# Sheet1.net
KiCad netlist of a schematic drawn in Altium Designer
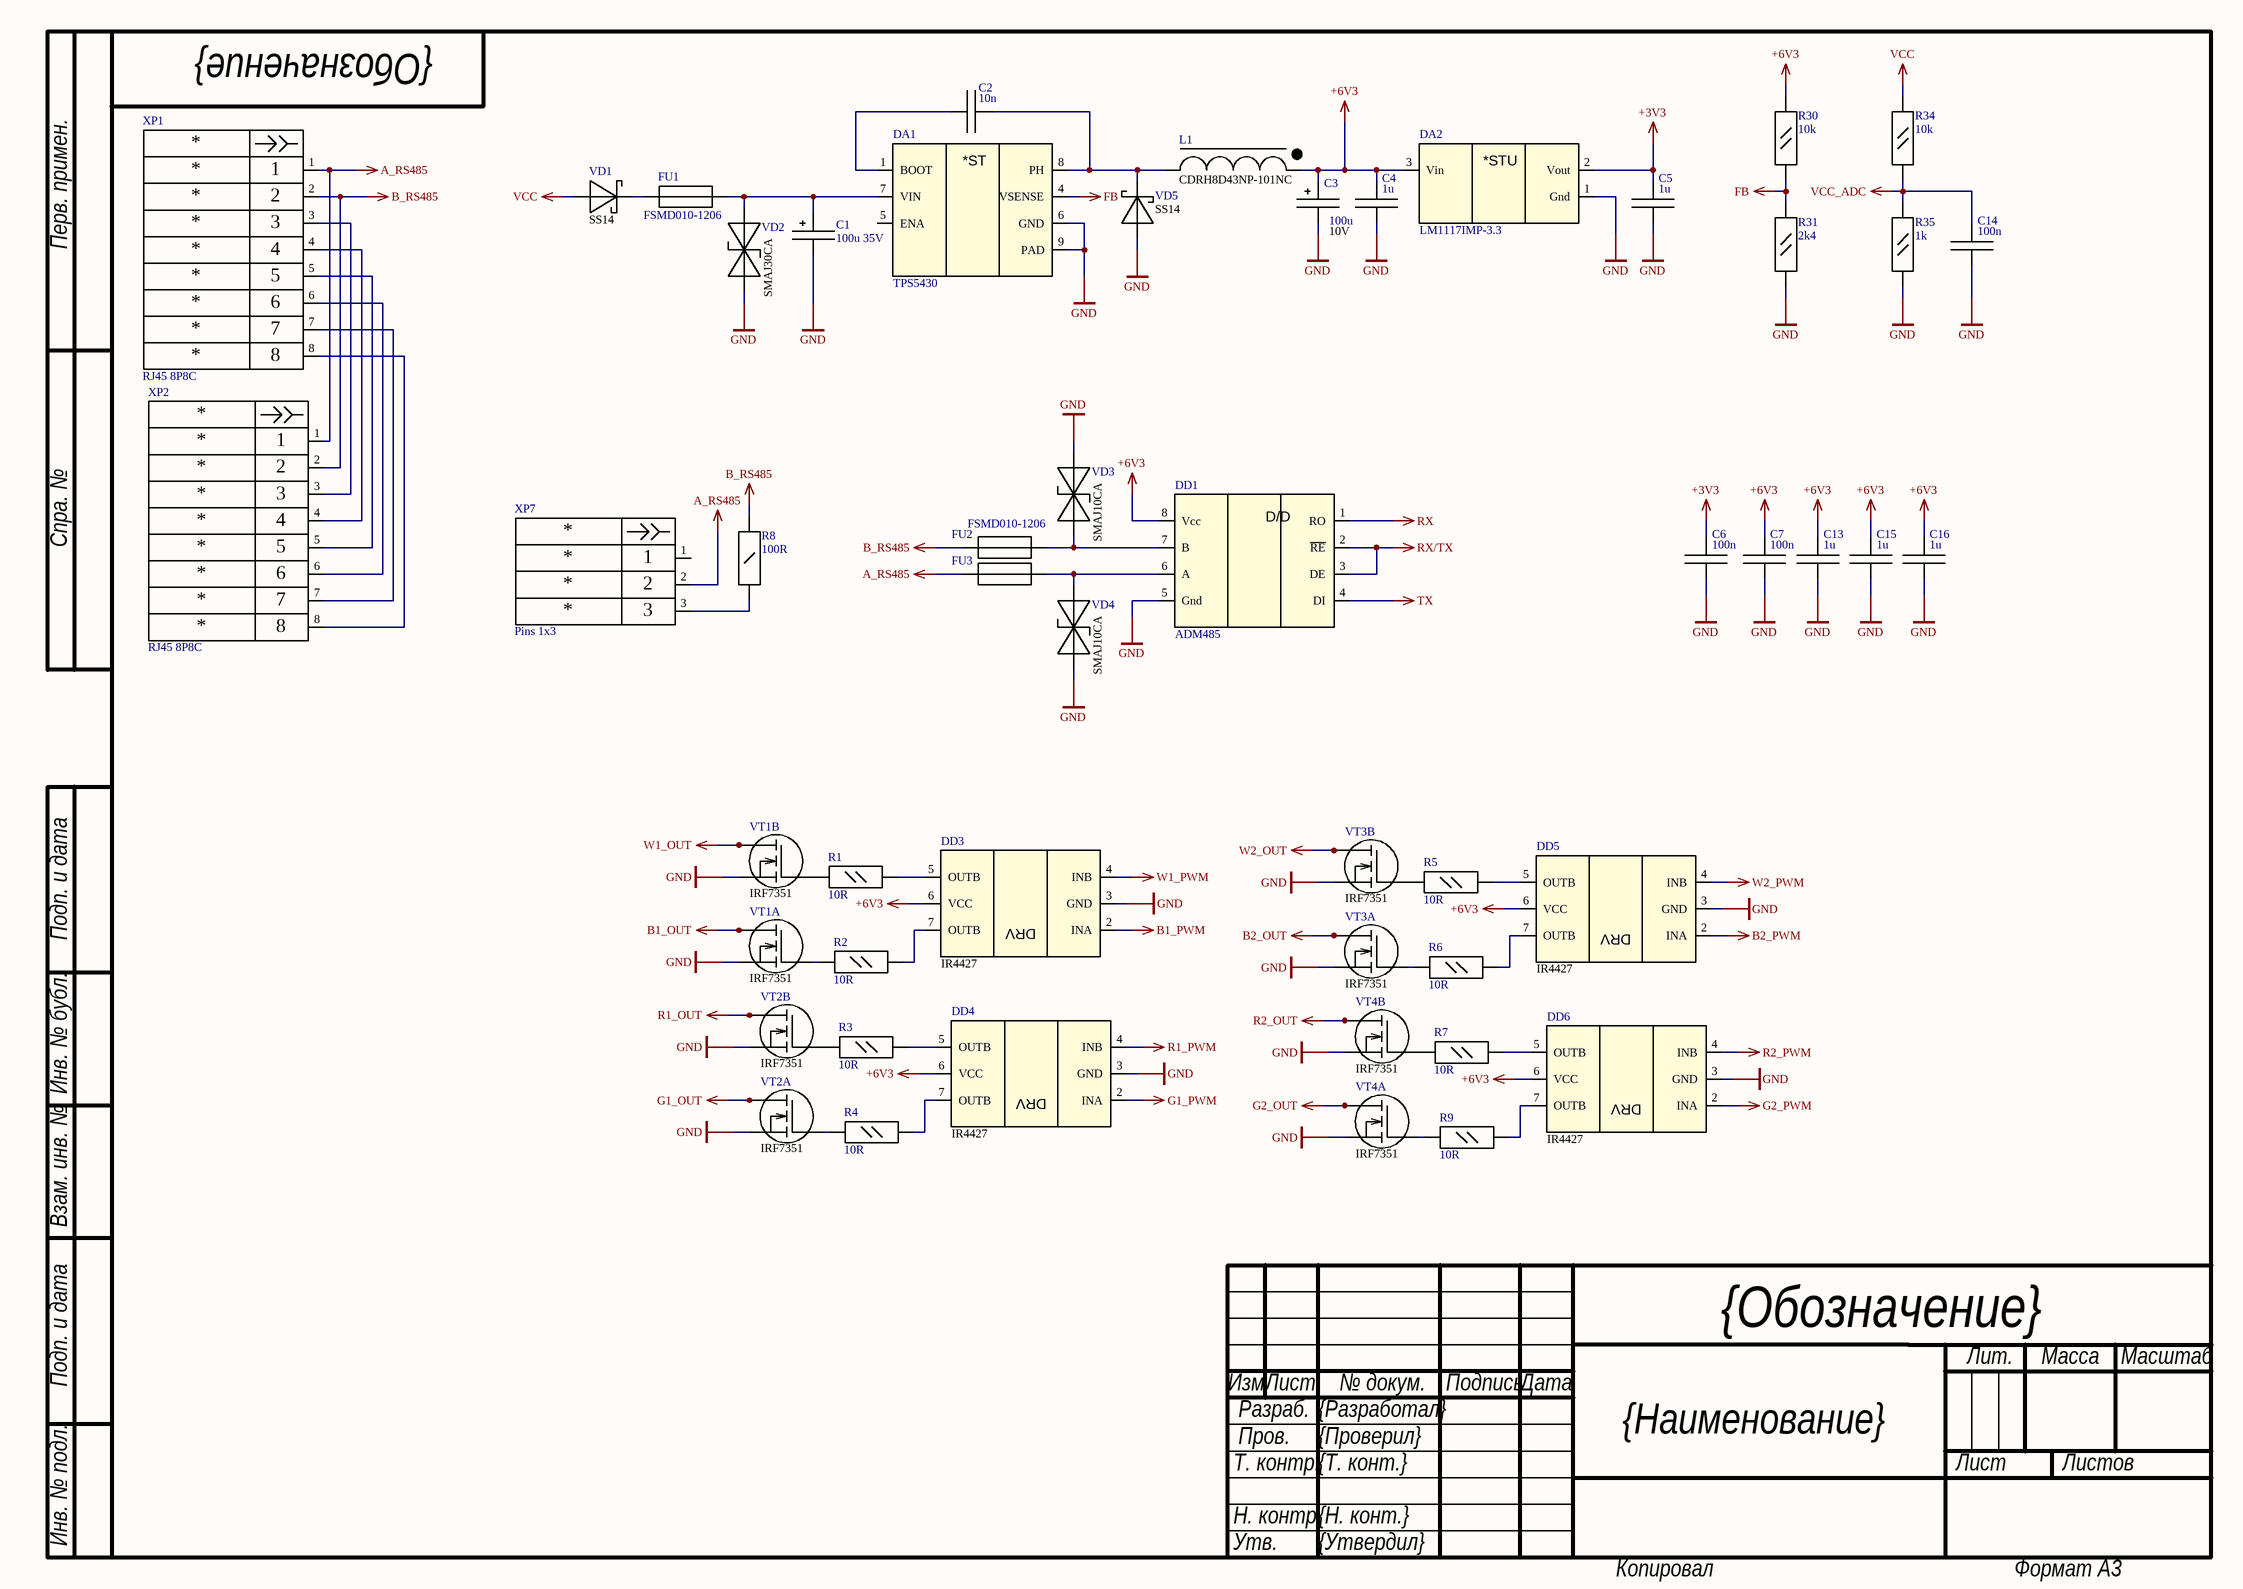
[diagram p0: Sheet1.SchDoc]

(export (version "E")
  (design (tool "Eeschema 10.0.6"))
  (components
    (comp (ref "C1")
      (value "100u 35V")
      (footprint "Cap electro d6.3x2.54mm")
      (libsource (lib "Россыпь") (part "ECap"))
    )
    (comp (ref "C2") (value "10n") (footprint "Cap Ceramic 0805") (libsource (lib "Россыпь") (part "CerCap")))
    (comp (ref "C3")
      (value "100u")
      (footprint "TECap D")
      (fields (field (name "COMMENTS") "10V"))
      (libsource (lib "Россыпь") (part "TECap"))
    )
    (comp (ref "C4") (value "1u") (footprint "Cap Ceramic 0805") (libsource (lib "Россыпь") (part "CerCap")))
    (comp (ref "C5") (value "1u") (footprint "Cap Ceramic 0805") (libsource (lib "Россыпь") (part "CerCap")))
    (comp (ref "C6")
      (value "100n")
      (footprint "Cap Ceramic 0805")
      (libsource (lib "Россыпь") (part "CerCap"))
    )
    (comp (ref "C7")
      (value "100n")
      (footprint "Cap Ceramic 0805")
      (libsource (lib "Россыпь") (part "CerCap"))
    )
    (comp (ref "C13") (value "1u") (footprint "Cap Ceramic 0805") (libsource (lib "Россыпь") (part "CerCap")))
    (comp (ref "C14")
      (value "100n")
      (footprint "Cap Ceramic 0805")
      (libsource (lib "Россыпь") (part "CerCap"))
    )
    (comp (ref "C15") (value "1u") (footprint "Cap Ceramic 0805") (libsource (lib "Россыпь") (part "CerCap")))
    (comp (ref "C16") (value "1u") (footprint "Cap Ceramic 0805") (libsource (lib "Россыпь") (part "CerCap")))
    (comp (ref "DA1")
      (value "TPS5430")
      (footprint "SO8 S1.27W6.00 GP")
      (libsource (lib "Россыпь") (part "TPS5430"))
    )
    (comp (ref "DA2")
      (value "LM1117IMP-3.3")
      (footprint "SOT-232")
      (libsource (lib "Россыпь") (part "LM1117IMP-x.x"))
    )
    (comp (ref "DD1")
      (value "ADM485")
      (footprint "SO8 S1.27W6.00")
      (libsource (lib "Россыпь") (part "ADM485"))
    )
    (comp (ref "DD3")
      (value "IR4427")
      (footprint "SO8 S1.27W6.00")
      (libsource (lib "Россыпь") (part "IR4427"))
    )
    (comp (ref "DD4")
      (value "IR4427")
      (footprint "SO8 S1.27W6.00")
      (libsource (lib "Россыпь") (part "IR4427"))
    )
    (comp (ref "DD5")
      (value "IR4427")
      (footprint "SO8 S1.27W6.00")
      (libsource (lib "Россыпь") (part "IR4427"))
    )
    (comp (ref "DD6")
      (value "IR4427")
      (footprint "SO8 S1.27W6.00")
      (libsource (lib "Россыпь") (part "IR4427"))
    )
    (comp (ref "FU1")
      (value "FSMD010-1206")
      (footprint "Fuse 1206")
      (libsource (lib "Россыпь") (part "FSMDxxx-1206"))
    )
    (comp (ref "FU2")
      (value "FSMD010-1206")
      (footprint "Fuse 1206")
      (libsource (lib "Россыпь") (part "FSMDxxx-1206"))
    )
    (comp (ref "FU3")
      (value "FSMD010-1206")
      (footprint "Fuse 1206")
      (libsource (lib "Россыпь") (part "FSMDxxx-1206"))
    )
    (comp (ref "L1")
      (value "CDRH8D43NP-101NC")
      (footprint "CDRH8D43NP-xxxNC")
      (libsource (lib "Россыпь") (part "CDRH8D43NP-xxxNC"))
    )
    (comp (ref "R1")
      (value "10R")
      (footprint "Resistor 0805")
      (libsource (lib "Россыпь") (part "Resistor 0,125W"))
    )
    (comp (ref "R2")
      (value "10R")
      (footprint "Resistor 0805")
      (libsource (lib "Россыпь") (part "Resistor 0,125W"))
    )
    (comp (ref "R3")
      (value "10R")
      (footprint "Resistor 0805")
      (libsource (lib "Россыпь") (part "Resistor 0,125W"))
    )
    (comp (ref "R4")
      (value "10R")
      (footprint "Resistor 0805")
      (libsource (lib "Россыпь") (part "Resistor 0,125W"))
    )
    (comp (ref "R5")
      (value "10R")
      (footprint "Resistor 0805")
      (libsource (lib "Россыпь") (part "Resistor 0,125W"))
    )
    (comp (ref "R6")
      (value "10R")
      (footprint "Resistor 0805")
      (libsource (lib "Россыпь") (part "Resistor 0,125W"))
    )
    (comp (ref "R7")
      (value "10R")
      (footprint "Resistor 0805")
      (libsource (lib "Россыпь") (part "Resistor 0,125W"))
    )
    (comp (ref "R8")
      (value "100R")
      (footprint "Resistor 1206")
      (libsource (lib "Россыпь") (part "Resistor 0,25W"))
    )
    (comp (ref "R9")
      (value "10R")
      (footprint "Resistor 0805")
      (libsource (lib "Россыпь") (part "Resistor 0,125W"))
    )
    (comp (ref "R30")
      (value "10k")
      (footprint "Resistor 0805")
      (libsource (lib "Россыпь") (part "Resistor 0,125W"))
    )
    (comp (ref "R31")
      (value "2k4")
      (footprint "Resistor 0805")
      (libsource (lib "Россыпь") (part "Resistor 0,125W"))
    )
    (comp (ref "R34")
      (value "10k")
      (footprint "Resistor 0805")
      (libsource (lib "Россыпь") (part "Resistor 0,125W"))
    )
    (comp (ref "R35")
      (value "1k")
      (footprint "Resistor 0805")
      (libsource (lib "Россыпь") (part "Resistor 0,125W"))
    )
    (comp (ref "VD1") (value "SS14") (footprint "DO-214AC SMA") (libsource (lib "Россыпь") (part "SS14")))
    (comp (ref "VD2")
      (value "SMAJ30CA")
      (footprint "DO-214AC SMA")
      (libsource (lib "Россыпь") (part "SMAJxxCA"))
    )
    (comp (ref "VD3")
      (value "SMAJ10CA")
      (footprint "DO-214AC SMA")
      (libsource (lib "Россыпь") (part "SMAJxxCA"))
    )
    (comp (ref "VD4")
      (value "SMAJ10CA")
      (footprint "DO-214AC SMA")
      (libsource (lib "Россыпь") (part "SMAJxxCA"))
    )
    (comp (ref "VD5") (value "SS14") (footprint "DO-214AC SMA") (libsource (lib "Россыпь") (part "SS14")))
    (comp (ref "VT1")
      (value "IRF7351")
      (footprint "SO8 S1.27W6.00")
      (libsource (lib "Россыпь") (part "IRF7351"))
    )
    (comp (ref "VT2")
      (value "IRF7351")
      (footprint "SO8 S1.27W6.00")
      (libsource (lib "Россыпь") (part "IRF7351"))
    )
    (comp (ref "VT3")
      (value "IRF7351")
      (footprint "SO8 S1.27W6.00")
      (libsource (lib "Россыпь") (part "IRF7351"))
    )
    (comp (ref "VT4")
      (value "IRF7351")
      (footprint "SO8 S1.27W6.00")
      (libsource (lib "Россыпь") (part "IRF7351"))
    )
    (comp (ref "XP1")
      (value "RJ45 8P8C")
      (footprint "RJ45 8P8C")
      (fields
        (field (name "NAME1") "*")
        (field (name "NAME2") "*")
        (field (name "NAME3") "*")
        (field (name "NAME") "*")
        (field (name "NAME4") "*")
        (field (name "NAME5") "*")
        (field (name "NAME6") "*")
        (field (name "NAME7") "*")
        (field (name "NAME8") "*")
      )
      (libsource (lib "Россыпь") (part "RJ45 8P8C"))
    )
    (comp (ref "XP2")
      (value "RJ45 8P8C")
      (footprint "RJ45 8P8C")
      (fields
        (field (name "NAME1") "*")
        (field (name "NAME2") "*")
        (field (name "NAME3") "*")
        (field (name "NAME") "*")
        (field (name "NAME4") "*")
        (field (name "NAME5") "*")
        (field (name "NAME6") "*")
        (field (name "NAME7") "*")
        (field (name "NAME8") "*")
      )
      (libsource (lib "Россыпь") (part "RJ45 8P8C"))
    )
    (comp (ref "XP7")
      (value "Pins 1x3")
      (footprint "Pins 1x3")
      (fields
        (field (name "NAME1") "*")
        (field (name "NAME") "*")
        (field (name "NAME2") "*")
        (field (name "NAME3") "*")
      )
      (libsource (lib "Россыпь") (part "Pins 1x3"))
    )
  )
  (nets
    (net (code "1") (name "+3V3") (class "Default")
      (node (ref "C5") (pin "2") (pinfunction "2_2") (pintype "passive"))
      (node (ref "C6") (pin "2") (pinfunction "2_2") (pintype "passive"))
      (node (ref "DA2") (pin "2") (pinfunction "Vout_2") (pintype "passive"))
    )
    (net (code "2") (name "+6V3") (class "Default")
      (node (ref "C13") (pin "2") (pinfunction "2_2") (pintype "passive"))
      (node (ref "C15") (pin "2") (pinfunction "2_2") (pintype "passive"))
      (node (ref "C16") (pin "2") (pinfunction "2_2") (pintype "passive"))
      (node (ref "C3") (pin "2") (pinfunction "2_2") (pintype "passive"))
      (node (ref "C4") (pin "2") (pinfunction "2_2") (pintype "passive"))
      (node (ref "C7") (pin "2") (pinfunction "2_2") (pintype "passive"))
      (node (ref "DA2") (pin "3") (pinfunction "Vin_3") (pintype "passive"))
      (node (ref "DD1") (pin "8") (pinfunction "Vcc_8") (pintype "passive"))
      (node (ref "DD3") (pin "6") (pinfunction "VCC_6") (pintype "passive"))
      (node (ref "DD4") (pin "6") (pinfunction "VCC_6") (pintype "passive"))
      (node (ref "DD5") (pin "6") (pinfunction "VCC_6") (pintype "passive"))
      (node (ref "DD6") (pin "6") (pinfunction "VCC_6") (pintype "passive"))
      (node (ref "L1") (pin "1") (pinfunction "1_1") (pintype "passive"))
      (node (ref "R30") (pin "1") (pinfunction "1_1") (pintype "passive"))
    )
    (net (code "3") (name "A_RS485") (class "Default")
      (node (ref "FU3") (pin "1") (pinfunction "1_1") (pintype "passive"))
      (node (ref "XP1") (pin "1") (pinfunction "1_1") (pintype "passive"))
      (node (ref "XP2") (pin "1") (pinfunction "1_1") (pintype "passive"))
      (node (ref "XP7") (pin "2") (pinfunction "2_2") (pintype "passive"))
    )
    (net (code "4") (name "B1_OUT") (class "Default")
      (node (ref "VT1") (pin "7") (pinfunction "D1_7") (pintype "passive"))
      (node (ref "VT1") (pin "8") (pinfunction "D1_8") (pintype "passive"))
    )
    (net (code "5") (name "B1_PWM") (class "Default")
      (node (ref "DD3") (pin "2") (pinfunction "INA_2") (pintype "passive"))
    )
    (net (code "6") (name "B2_OUT") (class "Default")
      (node (ref "VT3") (pin "7") (pinfunction "D1_7") (pintype "passive"))
      (node (ref "VT3") (pin "8") (pinfunction "D1_8") (pintype "passive"))
    )
    (net (code "7") (name "B2_PWM") (class "Default")
      (node (ref "DD5") (pin "2") (pinfunction "INA_2") (pintype "passive"))
    )
    (net (code "8") (name "B_RS485") (class "Default")
      (node (ref "FU2") (pin "1") (pinfunction "1_1") (pintype "passive"))
      (node (ref "R8") (pin "2") (pinfunction "2_2") (pintype "passive"))
      (node (ref "XP1") (pin "2") (pinfunction "2_2") (pintype "passive"))
      (node (ref "XP2") (pin "2") (pinfunction "2_2") (pintype "passive"))
    )
    (net (code "9") (name "FB") (class "Default")
      (node (ref "DA1") (pin "4") (pinfunction "VSENSE_4") (pintype "passive"))
      (node (ref "R30") (pin "2") (pinfunction "2_2") (pintype "passive"))
      (node (ref "R31") (pin "1") (pinfunction "1_1") (pintype "passive"))
    )
    (net (code "10") (name "G1_OUT") (class "Default")
      (node (ref "VT2") (pin "7") (pinfunction "D1_7") (pintype "passive"))
      (node (ref "VT2") (pin "8") (pinfunction "D1_8") (pintype "passive"))
    )
    (net (code "11") (name "G1_PWM") (class "Default")
      (node (ref "DD4") (pin "2") (pinfunction "INA_2") (pintype "passive"))
    )
    (net (code "12") (name "G2_OUT") (class "Default")
      (node (ref "VT4") (pin "7") (pinfunction "D1_7") (pintype "passive"))
      (node (ref "VT4") (pin "8") (pinfunction "D1_8") (pintype "passive"))
    )
    (net (code "13") (name "G2_PWM") (class "Default")
      (node (ref "DD6") (pin "2") (pinfunction "INA_2") (pintype "passive"))
    )
    (net (code "14") (name "GND") (class "Default")
      (node (ref "C1") (pin "1") (pinfunction "1_1") (pintype "passive"))
      (node (ref "C13") (pin "1") (pinfunction "1_1") (pintype "passive"))
      (node (ref "C14") (pin "1") (pinfunction "1_1") (pintype "passive"))
      (node (ref "C15") (pin "1") (pinfunction "1_1") (pintype "passive"))
      (node (ref "C16") (pin "1") (pinfunction "1_1") (pintype "passive"))
      (node (ref "C3") (pin "1") (pinfunction "1_1") (pintype "passive"))
      (node (ref "C4") (pin "1") (pinfunction "1_1") (pintype "passive"))
      (node (ref "C5") (pin "1") (pinfunction "1_1") (pintype "passive"))
      (node (ref "C6") (pin "1") (pinfunction "1_1") (pintype "passive"))
      (node (ref "C7") (pin "1") (pinfunction "1_1") (pintype "passive"))
      (node (ref "DA1") (pin "6") (pinfunction "GND_6") (pintype "passive"))
      (node (ref "DA1") (pin "9") (pinfunction "PAD_9") (pintype "passive"))
      (node (ref "DA2") (pin "1") (pinfunction "Gnd_1") (pintype "passive"))
      (node (ref "DD1") (pin "5") (pinfunction "Gnd_5") (pintype "passive"))
      (node (ref "DD3") (pin "3") (pinfunction "GND_3") (pintype "passive"))
      (node (ref "DD4") (pin "3") (pinfunction "GND_3") (pintype "passive"))
      (node (ref "DD5") (pin "3") (pinfunction "GND_3") (pintype "passive"))
      (node (ref "DD6") (pin "3") (pinfunction "GND_3") (pintype "passive"))
      (node (ref "R31") (pin "2") (pinfunction "2_2") (pintype "passive"))
      (node (ref "R35") (pin "2") (pinfunction "2_2") (pintype "passive"))
      (node (ref "VD2") (pin "1") (pinfunction "1_1") (pintype "passive"))
      (node (ref "VD3") (pin "1") (pinfunction "1_1") (pintype "passive"))
      (node (ref "VD4") (pin "1") (pinfunction "1_1") (pintype "passive"))
      (node (ref "VD5") (pin "1") (pinfunction "A_1") (pintype "passive"))
      (node (ref "VT1") (pin "1") (pinfunction "S1_1") (pintype "passive"))
      (node (ref "VT1") (pin "3") (pinfunction "S2_3") (pintype "passive"))
      (node (ref "VT2") (pin "1") (pinfunction "S1_1") (pintype "passive"))
      (node (ref "VT2") (pin "3") (pinfunction "S2_3") (pintype "passive"))
      (node (ref "VT3") (pin "1") (pinfunction "S1_1") (pintype "passive"))
      (node (ref "VT3") (pin "3") (pinfunction "S2_3") (pintype "passive"))
      (node (ref "VT4") (pin "1") (pinfunction "S1_1") (pintype "passive"))
      (node (ref "VT4") (pin "3") (pinfunction "S2_3") (pintype "passive"))
    )
    (net (code "15") (name "Net-(DA1-BOOT)") (class "Default")
      (node (ref "C2") (pin "1") (pinfunction "1_1") (pintype "passive"))
      (node (ref "DA1") (pin "1") (pinfunction "BOOT_1") (pintype "passive"))
    )
    (net (code "16") (name "Net-(DA1-PH)") (class "Default")
      (node (ref "C2") (pin "2") (pinfunction "2_2") (pintype "passive"))
      (node (ref "DA1") (pin "8") (pinfunction "PH_8") (pintype "passive"))
      (node (ref "L1") (pin "2") (pinfunction "2_2") (pintype "passive"))
      (node (ref "VD5") (pin "2") (pinfunction "K_2") (pintype "passive"))
    )
    (net (code "17") (name "Net-(DA1-VIN)") (class "Default")
      (node (ref "C1") (pin "2") (pinfunction "2_2") (pintype "passive"))
      (node (ref "DA1") (pin "7") (pinfunction "VIN_7") (pintype "passive"))
      (node (ref "FU1") (pin "2") (pinfunction "2_2") (pintype "passive"))
      (node (ref "VD2") (pin "2") (pinfunction "2_2") (pintype "passive"))
    )
    (net (code "18") (name "Net-(DD1-A)") (class "Default")
      (node (ref "DD1") (pin "6") (pinfunction "A_6") (pintype "passive"))
      (node (ref "FU3") (pin "2") (pinfunction "2_2") (pintype "passive"))
      (node (ref "VD4") (pin "2") (pinfunction "2_2") (pintype "passive"))
    )
    (net (code "19") (name "Net-(DD1-B)") (class "Default")
      (node (ref "DD1") (pin "7") (pinfunction "B_7") (pintype "passive"))
      (node (ref "FU2") (pin "2") (pinfunction "2_2") (pintype "passive"))
      (node (ref "VD3") (pin "2") (pinfunction "2_2") (pintype "passive"))
    )
    (net (code "20") (name "Net-(DD3-OUTB-Pad5)") (class "Default")
      (node (ref "DD3") (pin "5") (pinfunction "OUTB_5") (pintype "passive"))
      (node (ref "R1") (pin "2") (pinfunction "2_2") (pintype "passive"))
    )
    (net (code "21") (name "Net-(DD3-OUTB-Pad7)") (class "Default")
      (node (ref "DD3") (pin "7") (pinfunction "OUTB_7") (pintype "passive"))
      (node (ref "R2") (pin "2") (pinfunction "2_2") (pintype "passive"))
    )
    (net (code "22") (name "Net-(DD4-OUTB-Pad5)") (class "Default")
      (node (ref "DD4") (pin "5") (pinfunction "OUTB_5") (pintype "passive"))
      (node (ref "R3") (pin "2") (pinfunction "2_2") (pintype "passive"))
    )
    (net (code "23") (name "Net-(DD4-OUTB-Pad7)") (class "Default")
      (node (ref "DD4") (pin "7") (pinfunction "OUTB_7") (pintype "passive"))
      (node (ref "R4") (pin "2") (pinfunction "2_2") (pintype "passive"))
    )
    (net (code "24") (name "Net-(DD5-OUTB-Pad5)") (class "Default")
      (node (ref "DD5") (pin "5") (pinfunction "OUTB_5") (pintype "passive"))
      (node (ref "R5") (pin "2") (pinfunction "2_2") (pintype "passive"))
    )
    (net (code "25") (name "Net-(DD5-OUTB-Pad7)") (class "Default")
      (node (ref "DD5") (pin "7") (pinfunction "OUTB_7") (pintype "passive"))
      (node (ref "R6") (pin "2") (pinfunction "2_2") (pintype "passive"))
    )
    (net (code "26") (name "Net-(DD6-OUTB-Pad5)") (class "Default")
      (node (ref "DD6") (pin "5") (pinfunction "OUTB_5") (pintype "passive"))
      (node (ref "R7") (pin "2") (pinfunction "2_2") (pintype "passive"))
    )
    (net (code "27") (name "Net-(DD6-OUTB-Pad7)") (class "Default")
      (node (ref "DD6") (pin "7") (pinfunction "OUTB_7") (pintype "passive"))
      (node (ref "R9") (pin "2") (pinfunction "2_2") (pintype "passive"))
    )
    (net (code "28") (name "Net-(R8-Pad1)") (class "Default")
      (node (ref "R8") (pin "1") (pinfunction "1_1") (pintype "passive"))
      (node (ref "XP7") (pin "3") (pinfunction "3_3") (pintype "passive"))
    )
    (net (code "29") (name "Net-(VD1-K)") (class "Default")
      (node (ref "FU1") (pin "1") (pinfunction "1_1") (pintype "passive"))
      (node (ref "VD1") (pin "2") (pinfunction "K_2") (pintype "passive"))
    )
    (net (code "30") (name "Net-(VT1A-G1)") (class "Default")
      (node (ref "R2") (pin "1") (pinfunction "1_1") (pintype "passive"))
      (node (ref "VT1") (pin "2") (pinfunction "G1_2") (pintype "passive"))
    )
    (net (code "31") (name "Net-(VT1B-G2)") (class "Default")
      (node (ref "R1") (pin "1") (pinfunction "1_1") (pintype "passive"))
      (node (ref "VT1") (pin "4") (pinfunction "G2_4") (pintype "passive"))
    )
    (net (code "32") (name "Net-(VT2A-G1)") (class "Default")
      (node (ref "R4") (pin "1") (pinfunction "1_1") (pintype "passive"))
      (node (ref "VT2") (pin "2") (pinfunction "G1_2") (pintype "passive"))
    )
    (net (code "33") (name "Net-(VT2B-G2)") (class "Default")
      (node (ref "R3") (pin "1") (pinfunction "1_1") (pintype "passive"))
      (node (ref "VT2") (pin "4") (pinfunction "G2_4") (pintype "passive"))
    )
    (net (code "34") (name "Net-(VT3A-G1)") (class "Default")
      (node (ref "R6") (pin "1") (pinfunction "1_1") (pintype "passive"))
      (node (ref "VT3") (pin "2") (pinfunction "G1_2") (pintype "passive"))
    )
    (net (code "35") (name "Net-(VT3B-G2)") (class "Default")
      (node (ref "R5") (pin "1") (pinfunction "1_1") (pintype "passive"))
      (node (ref "VT3") (pin "4") (pinfunction "G2_4") (pintype "passive"))
    )
    (net (code "36") (name "Net-(VT4A-G1)") (class "Default")
      (node (ref "R9") (pin "1") (pinfunction "1_1") (pintype "passive"))
      (node (ref "VT4") (pin "2") (pinfunction "G1_2") (pintype "passive"))
    )
    (net (code "37") (name "Net-(VT4B-G2)") (class "Default")
      (node (ref "R7") (pin "1") (pinfunction "1_1") (pintype "passive"))
      (node (ref "VT4") (pin "4") (pinfunction "G2_4") (pintype "passive"))
    )
    (net (code "38") (name "Net-(XP1-Pad3)") (class "Default")
      (node (ref "XP1") (pin "3") (pinfunction "3_3") (pintype "passive"))
      (node (ref "XP2") (pin "3") (pinfunction "3_3") (pintype "passive"))
    )
    (net (code "39") (name "Net-(XP1-Pad4)") (class "Default")
      (node (ref "XP1") (pin "4") (pinfunction "4_4") (pintype "passive"))
      (node (ref "XP2") (pin "4") (pinfunction "4_4") (pintype "passive"))
    )
    (net (code "40") (name "Net-(XP1-Pad5)") (class "Default")
      (node (ref "XP1") (pin "5") (pinfunction "5_5") (pintype "passive"))
      (node (ref "XP2") (pin "5") (pinfunction "5_5") (pintype "passive"))
    )
    (net (code "41") (name "Net-(XP1-Pad6)") (class "Default")
      (node (ref "XP1") (pin "6") (pinfunction "6_6") (pintype "passive"))
      (node (ref "XP2") (pin "6") (pinfunction "6_6") (pintype "passive"))
    )
    (net (code "42") (name "Net-(XP1-Pad7)") (class "Default")
      (node (ref "XP1") (pin "7") (pinfunction "7_7") (pintype "passive"))
      (node (ref "XP2") (pin "7") (pinfunction "7_7") (pintype "passive"))
    )
    (net (code "43") (name "Net-(XP1-Pad8)") (class "Default")
      (node (ref "XP1") (pin "8") (pinfunction "8_8") (pintype "passive"))
      (node (ref "XP2") (pin "8") (pinfunction "8_8") (pintype "passive"))
    )
    (net (code "44") (name "R1_OUT") (class "Default")
      (node (ref "VT2") (pin "5") (pinfunction "D1_5") (pintype "passive"))
      (node (ref "VT2") (pin "6") (pinfunction "D1_6") (pintype "passive"))
    )
    (net (code "45") (name "R1_PWM") (class "Default")
      (node (ref "DD4") (pin "4") (pinfunction "INB_4") (pintype "passive"))
    )
    (net (code "46") (name "R2_OUT") (class "Default")
      (node (ref "VT4") (pin "5") (pinfunction "D1_5") (pintype "passive"))
      (node (ref "VT4") (pin "6") (pinfunction "D1_6") (pintype "passive"))
    )
    (net (code "47") (name "R2_PWM") (class "Default")
      (node (ref "DD6") (pin "4") (pinfunction "INB_4") (pintype "passive"))
    )
    (net (code "48") (name "RX") (class "Default")
      (node (ref "DD1") (pin "1") (pinfunction "RO_1") (pintype "passive"))
    )
    (net (code "49") (name "RX{slash}TX") (class "Default")
      (node (ref "DD1") (pin "2") (pinfunction "RE_2") (pintype "passive"))
      (node (ref "DD1") (pin "3") (pinfunction "DE_3") (pintype "passive"))
    )
    (net (code "50") (name "TX") (class "Default")
      (node (ref "DD1") (pin "4") (pinfunction "DI_4") (pintype "passive"))
    )
    (net (code "51") (name "VCC") (class "Default")
      (node (ref "R34") (pin "1") (pinfunction "1_1") (pintype "passive"))
      (node (ref "VD1") (pin "1") (pinfunction "A_1") (pintype "passive"))
    )
    (net (code "52") (name "VCC_ADC") (class "Default")
      (node (ref "C14") (pin "2") (pinfunction "2_2") (pintype "passive"))
      (node (ref "R34") (pin "2") (pinfunction "2_2") (pintype "passive"))
      (node (ref "R35") (pin "1") (pinfunction "1_1") (pintype "passive"))
    )
    (net (code "53") (name "W1_OUT") (class "Default")
      (node (ref "VT1") (pin "5") (pinfunction "D1_5") (pintype "passive"))
      (node (ref "VT1") (pin "6") (pinfunction "D1_6") (pintype "passive"))
    )
    (net (code "54") (name "W1_PWM") (class "Default")
      (node (ref "DD3") (pin "4") (pinfunction "INB_4") (pintype "passive"))
    )
    (net (code "55") (name "W2_OUT") (class "Default")
      (node (ref "VT3") (pin "5") (pinfunction "D1_5") (pintype "passive"))
      (node (ref "VT3") (pin "6") (pinfunction "D1_6") (pintype "passive"))
    )
    (net (code "56") (name "W2_PWM") (class "Default")
      (node (ref "DD5") (pin "4") (pinfunction "INB_4") (pintype "passive"))
    )
    (net (code "57") (name "unconnected-(DA1-ENA-Pad5)") (class "Default")
      (node (ref "DA1") (pin "5") (pinfunction "ENA_5") (pintype "passive"))
    )
    (net (code "58") (name "unconnected-(DA1-NC-Pad2)") (class "Default")
      (node (ref "DA1") (pin "2") (pinfunction "NC_2") (pintype "passive"))
    )
    (net (code "59") (name "unconnected-(DA1-NC-Pad3)") (class "Default")
      (node (ref "DA1") (pin "3") (pinfunction "NC_3") (pintype "passive"))
    )
    (net (code "60") (name "unconnected-(XP7-Pad1)") (class "Default")
      (node (ref "XP7") (pin "1") (pinfunction "1_1") (pintype "passive"))
    )
  )
)
